# Swarm_Bot_Overall.net
KiCad netlist of a schematic drawn in EAGLE
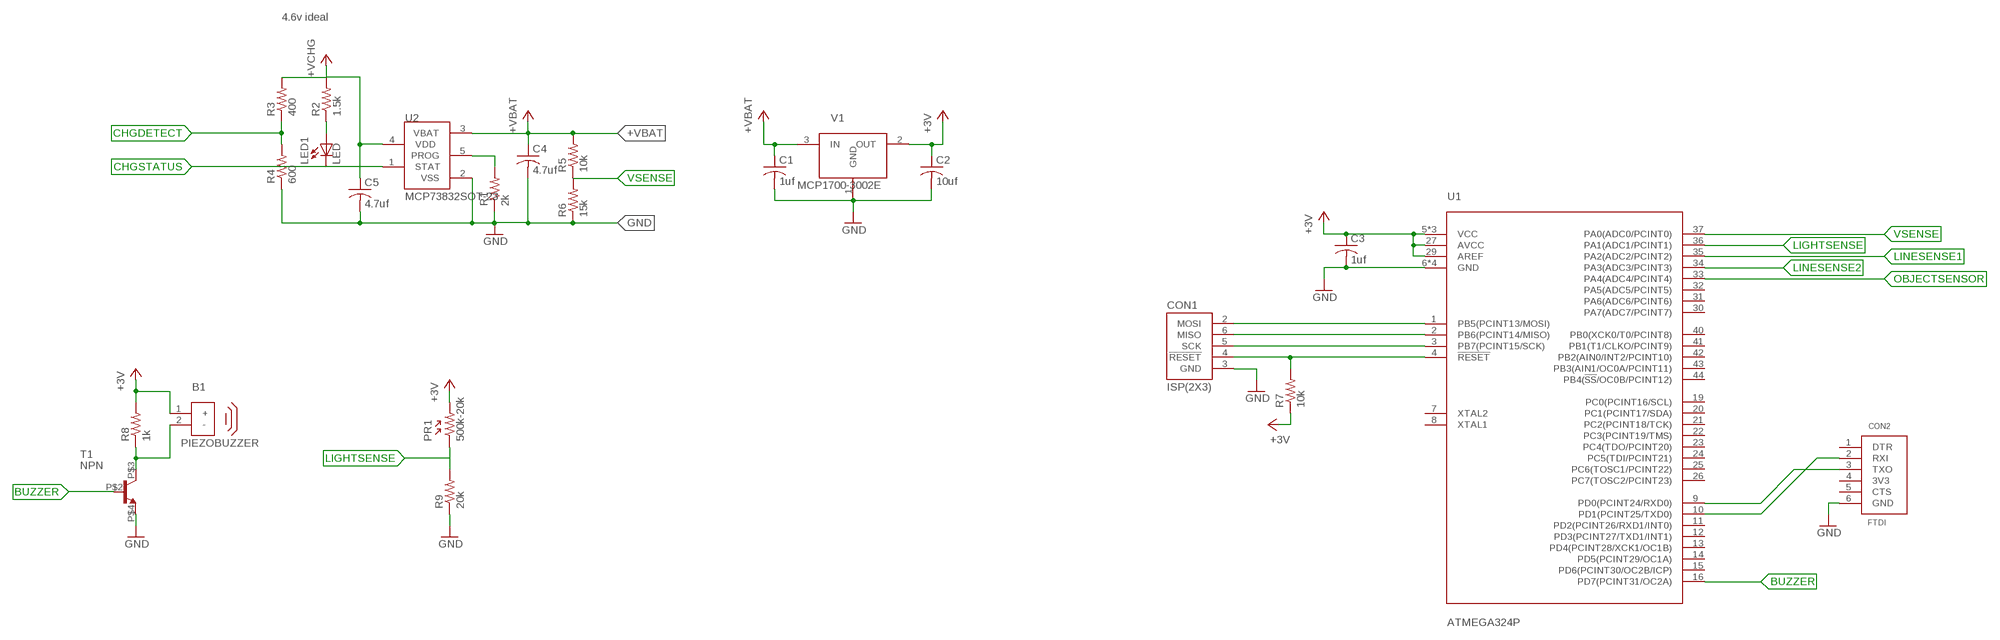
[diagram p0: schematic, sheet 1]

(export (version "E")
  (design (tool "Eeschema 10.0.6"))
  (components
    (comp (ref "B1")
      (value "PIEZOBUZZER")
      (footprint "eagle-import:PIEZOBUZZER")
      (libsource (lib "eagle-import") (part "PIEZOBUZZER"))
    )
    (comp (ref "C1")
      (value "1uf")
      (footprint "eagle-import:0603")
      (libsource (lib "eagle-import") (part "CAP0603"))
    )
    (comp (ref "C2")
      (value "10uf")
      (footprint "eagle-import:0805")
      (libsource (lib "eagle-import") (part "CAP0805"))
    )
    (comp (ref "C3")
      (value "1uf")
      (footprint "eagle-import:0603")
      (libsource (lib "eagle-import") (part "CAP0603"))
    )
    (comp (ref "C4")
      (value "4.7uf")
      (footprint "eagle-import:0603")
      (libsource (lib "eagle-import") (part "CAP0603"))
    )
    (comp (ref "C5")
      (value "4.7uf")
      (footprint "eagle-import:0603")
      (libsource (lib "eagle-import") (part "CAP0603"))
    )
    (comp (ref "CON1")
      (value "ISP(2X3)")
      (footprint "eagle-import:PINHEADER(2X3)")
      (libsource (lib "eagle-import") (part "ISP(2X3)"))
    )
    (comp (ref "CON2")
      (value "FTDI")
      (footprint "eagle-import:PINHEADER(1X6)")
      (libsource (lib "eagle-import") (part "FTDI"))
    )
    (comp (ref "LED1")
      (value "LED")
      (footprint "eagle-import:0603")
      (libsource (lib "eagle-import") (part "LED"))
    )
    (comp (ref "PR1")
      (value "500k-20k")
      (footprint "eagle-import:CDSPHOTOCELL")
      (libsource (lib "eagle-import") (part "CDSPHOTORESISTOR"))
    )
    (comp (ref "R1")
      (value "2k")
      (footprint "eagle-import:0603")
      (libsource (lib "eagle-import") (part "RES0603"))
    )
    (comp (ref "R2")
      (value "1.5k")
      (footprint "eagle-import:0603")
      (libsource (lib "eagle-import") (part "RES0603"))
    )
    (comp (ref "R3")
      (value "400")
      (footprint "eagle-import:0603")
      (libsource (lib "eagle-import") (part "RES0603"))
    )
    (comp (ref "R4")
      (value "600")
      (footprint "eagle-import:0603")
      (libsource (lib "eagle-import") (part "RES0603"))
    )
    (comp (ref "R5")
      (value "10k")
      (footprint "eagle-import:0603")
      (libsource (lib "eagle-import") (part "RES0603"))
    )
    (comp (ref "R6")
      (value "15k")
      (footprint "eagle-import:0603")
      (libsource (lib "eagle-import") (part "RES0603"))
    )
    (comp (ref "R7")
      (value "10k")
      (footprint "eagle-import:0603")
      (libsource (lib "eagle-import") (part "RES0603"))
    )
    (comp (ref "R8")
      (value "1k")
      (footprint "eagle-import:0603")
      (libsource (lib "eagle-import") (part "RES0603"))
    )
    (comp (ref "R9")
      (value "20k")
      (footprint "eagle-import:0603")
      (libsource (lib "eagle-import") (part "RES0603"))
    )
    (comp (ref "T1")
      (value "NPN")
      (footprint "eagle-import:DUMMY")
      (libsource (lib "eagle-import") (part "NPN"))
    )
    (comp (ref "U1")
      (value "ATMEGA324P")
      (footprint "eagle-import:TQFP44")
      (libsource (lib "eagle-import") (part "ATMEGA324P"))
    )
    (comp (ref "U2")
      (value "MCP73832SOT-23")
      (footprint "eagle-import:(OT)SOT-23(5PAD)")
      (libsource (lib "eagle-import") (part "MCP73832SOT-23"))
    )
    (comp (ref "V1")
      (value "MCP1700-3002E")
      (footprint "eagle-import:(TT_NB)SOT-23(3PAD)")
      (libsource (lib "eagle-import") (part "MCP1700-3002E"))
    )
  )
  (nets
    (net (code "1") (name "+3V") (class "Default")
      (node (ref "B1") (pin "1") (pinfunction "+_1") (pintype "bidirectional"))
      (node (ref "C2") (pin "1") (pinfunction "1_1") (pintype "passive"))
      (node (ref "C3") (pin "1") (pinfunction "1_1") (pintype "passive"))
      (node (ref "PR1") (pin "2") (pinfunction "2_2") (pintype "passive"))
      (node (ref "R7") (pin "1") (pinfunction "1_1") (pintype "passive"))
      (node (ref "R8") (pin "2") (pinfunction "2_2") (pintype "passive"))
      (node (ref "U1") (pin "17") (pinfunction "VCC_17") (pintype "bidirectional"))
      (node (ref "U1") (pin "27") (pinfunction "AVCC_27") (pintype "bidirectional"))
      (node (ref "U1") (pin "29") (pinfunction "AREF_29") (pintype "bidirectional"))
      (node (ref "U1") (pin "38") (pinfunction "VCC_38") (pintype "bidirectional"))
      (node (ref "U1") (pin "5") (pinfunction "VCC_5") (pintype "bidirectional"))
      (node (ref "V1") (pin "2") (pinfunction "OUT_2") (pintype "bidirectional"))
    )
    (net (code "2") (name "+VBAT") (class "Default")
      (node (ref "C1") (pin "1") (pinfunction "1_1") (pintype "passive"))
      (node (ref "C4") (pin "1") (pinfunction "1_1") (pintype "passive"))
      (node (ref "R5") (pin "2") (pinfunction "2_2") (pintype "passive"))
      (node (ref "U2") (pin "3") (pinfunction "VBAT_3") (pintype "bidirectional"))
      (node (ref "V1") (pin "3") (pinfunction "IN_3") (pintype "bidirectional"))
    )
    (net (code "3") (name "+VCHG") (class "Default")
      (node (ref "C5") (pin "1") (pinfunction "1_1") (pintype "passive"))
      (node (ref "R2") (pin "2") (pinfunction "2_2") (pintype "passive"))
      (node (ref "R3") (pin "2") (pinfunction "2_2") (pintype "passive"))
      (node (ref "U2") (pin "4") (pinfunction "VDD_4") (pintype "bidirectional"))
    )
    (net (code "4") (name "BUZZER") (class "Default")
      (node (ref "T1") (pin "P$2") (pinfunction "B_P$2") (pintype "passive"))
      (node (ref "U1") (pin "16") (pinfunction "PD7(PCINT31/OC2A)_16") (pintype "bidirectional"))
    )
    (net (code "5") (name "CHGDETECT") (class "Default")
      (node (ref "R3") (pin "1") (pinfunction "1_1") (pintype "passive"))
      (node (ref "R4") (pin "2") (pinfunction "2_2") (pintype "passive"))
    )
    (net (code "6") (name "CHGSTATUS") (class "Default")
      (node (ref "LED1") (pin "1") (pinfunction "C_1") (pintype "passive"))
      (node (ref "U2") (pin "1") (pinfunction "STAT_1") (pintype "bidirectional"))
    )
    (net (code "7") (name "GND") (class "Default")
      (node (ref "C1") (pin "2") (pinfunction "2_2") (pintype "passive"))
      (node (ref "C2") (pin "2") (pinfunction "2_2") (pintype "passive"))
      (node (ref "C3") (pin "2") (pinfunction "2_2") (pintype "passive"))
      (node (ref "C4") (pin "2") (pinfunction "2_2") (pintype "passive"))
      (node (ref "C5") (pin "2") (pinfunction "2_2") (pintype "passive"))
      (node (ref "CON1") (pin "3") (pinfunction "GND_3") (pintype "bidirectional"))
      (node (ref "CON2") (pin "6") (pinfunction "GND_6") (pintype "bidirectional"))
      (node (ref "R1") (pin "1") (pinfunction "1_1") (pintype "passive"))
      (node (ref "R4") (pin "1") (pinfunction "1_1") (pintype "passive"))
      (node (ref "R6") (pin "1") (pinfunction "1_1") (pintype "passive"))
      (node (ref "R9") (pin "1") (pinfunction "1_1") (pintype "passive"))
      (node (ref "T1") (pin "P$4") (pinfunction "E_P$4") (pintype "passive"))
      (node (ref "U1") (pin "18") (pinfunction "GND_18") (pintype "bidirectional"))
      (node (ref "U1") (pin "28") (pinfunction "GND_28") (pintype "bidirectional"))
      (node (ref "U1") (pin "39") (pinfunction "GND_39") (pintype "bidirectional"))
      (node (ref "U1") (pin "6") (pinfunction "GND_6") (pintype "bidirectional"))
      (node (ref "U2") (pin "2") (pinfunction "VSS_2") (pintype "bidirectional"))
      (node (ref "V1") (pin "1") (pinfunction "GND_1") (pintype "bidirectional"))
    )
    (net (code "8") (name "LIGHTSENSE") (class "Default")
      (node (ref "PR1") (pin "1") (pinfunction "1_1") (pintype "passive"))
      (node (ref "R9") (pin "2") (pinfunction "2_2") (pintype "passive"))
      (node (ref "U1") (pin "36") (pinfunction "PA1(ADC1/PCINT1)_36") (pintype "bidirectional"))
    )
    (net (code "9") (name "LINESENSE1") (class "Default")
      (node (ref "U1") (pin "35") (pinfunction "PA2(ADC2/PCINT2)_35") (pintype "bidirectional"))
    )
    (net (code "10") (name "LINESENSE2") (class "Default")
      (node (ref "U1") (pin "34") (pinfunction "PA3(ADC3/PCINT3)_34") (pintype "bidirectional"))
    )
    (net (code "11") (name "Net-(B1--)") (class "Default")
      (node (ref "B1") (pin "2") (pinfunction "-_2") (pintype "bidirectional"))
      (node (ref "R8") (pin "1") (pinfunction "1_1") (pintype "passive"))
      (node (ref "T1") (pin "P$3") (pinfunction "C_P$3") (pintype "passive"))
    )
    (net (code "12") (name "Net-(CON1-MISO)") (class "Default")
      (node (ref "CON1") (pin "6") (pinfunction "MISO_6") (pintype "bidirectional"))
      (node (ref "U1") (pin "2") (pinfunction "PB6(PCINT14/MISO)_2") (pintype "bidirectional"))
    )
    (net (code "13") (name "Net-(CON1-MOSI)") (class "Default")
      (node (ref "CON1") (pin "2") (pinfunction "MOSI_2") (pintype "bidirectional"))
      (node (ref "U1") (pin "1") (pinfunction "PB5(PCINT13/MOSI)_1") (pintype "bidirectional"))
    )
    (net (code "14") (name "Net-(CON1-SCK)") (class "Default")
      (node (ref "CON1") (pin "5") (pinfunction "SCK_5") (pintype "bidirectional"))
      (node (ref "U1") (pin "3") (pinfunction "PB7(PCINT15/SCK)_3") (pintype "bidirectional"))
    )
    (net (code "15") (name "Net-(CON1-~{RESET})") (class "Default")
      (node (ref "CON1") (pin "4") (pinfunction "~{RESET}_4") (pintype "bidirectional"))
      (node (ref "R7") (pin "2") (pinfunction "2_2") (pintype "passive"))
      (node (ref "U1") (pin "4") (pinfunction "~{RESET}_4") (pintype "bidirectional"))
    )
    (net (code "16") (name "Net-(CON2-RXI)") (class "Default")
      (node (ref "CON2") (pin "2") (pinfunction "RXI_2") (pintype "bidirectional"))
      (node (ref "U1") (pin "10") (pinfunction "PD1(PCINT25/TXD0)_10") (pintype "bidirectional"))
    )
    (net (code "17") (name "Net-(CON2-TXO)") (class "Default")
      (node (ref "CON2") (pin "3") (pinfunction "TXO_3") (pintype "bidirectional"))
      (node (ref "U1") (pin "9") (pinfunction "PD0(PCINT24/RXD0)_9") (pintype "bidirectional"))
    )
    (net (code "18") (name "Net-(LED1-A)") (class "Default")
      (node (ref "LED1") (pin "2") (pinfunction "A_2") (pintype "passive"))
      (node (ref "R2") (pin "1") (pinfunction "1_1") (pintype "passive"))
    )
    (net (code "19") (name "Net-(U2-PROG)") (class "Default")
      (node (ref "R1") (pin "2") (pinfunction "2_2") (pintype "passive"))
      (node (ref "U2") (pin "5") (pinfunction "PROG_5") (pintype "bidirectional"))
    )
    (net (code "20") (name "OBJECTSENSOR") (class "Default")
      (node (ref "U1") (pin "33") (pinfunction "PA4(ADC4/PCINT4)_33") (pintype "bidirectional"))
    )
    (net (code "21") (name "VSENSE") (class "Default")
      (node (ref "R5") (pin "1") (pinfunction "1_1") (pintype "passive"))
      (node (ref "R6") (pin "2") (pinfunction "2_2") (pintype "passive"))
      (node (ref "U1") (pin "37") (pinfunction "PA0(ADC0/PCINT0)_37") (pintype "bidirectional"))
    )
    (net (code "22") (name "unconnected-(CON2-3V3-Pad4)") (class "Default")
      (node (ref "CON2") (pin "4") (pinfunction "3V3_4") (pintype "bidirectional"))
    )
    (net (code "23") (name "unconnected-(CON2-CTS-Pad5)") (class "Default")
      (node (ref "CON2") (pin "5") (pinfunction "CTS_5") (pintype "bidirectional"))
    )
    (net (code "24") (name "unconnected-(CON2-DTR-Pad1)") (class "Default")
      (node (ref "CON2") (pin "1") (pinfunction "DTR_1") (pintype "bidirectional"))
    )
    (net (code "25") (name "unconnected-(U1-PA5(ADC5{slash}PCINT5)-Pad32)") (class "Default")
      (node (ref "U1") (pin "32") (pinfunction "PA5(ADC5/PCINT5)_32") (pintype "bidirectional"))
    )
    (net (code "26") (name "unconnected-(U1-PA6(ADC6{slash}PCINT6)-Pad31)") (class "Default")
      (node (ref "U1") (pin "31") (pinfunction "PA6(ADC6/PCINT6)_31") (pintype "bidirectional"))
    )
    (net (code "27") (name "unconnected-(U1-PA7(ADC7{slash}PCINT7)-Pad30)") (class "Default")
      (node (ref "U1") (pin "30") (pinfunction "PA7(ADC7/PCINT7)_30") (pintype "bidirectional"))
    )
    (net (code "28") (name "unconnected-(U1-PB0(XCK0{slash}T0{slash}PCINT8)-Pad40)") (class "Default")
      (node (ref "U1") (pin "40") (pinfunction "PB0(XCK0/T0/PCINT8)_40") (pintype "bidirectional"))
    )
    (net (code "29") (name "unconnected-(U1-PB1(T1{slash}CLKO{slash}PCINT9)-Pad41)") (class "Default")
      (node (ref "U1") (pin "41") (pinfunction "PB1(T1/CLKO/PCINT9)_41") (pintype "bidirectional"))
    )
    (net (code "30") (name "unconnected-(U1-PB2(AIN0{slash}INT2{slash}PCINT10)-Pad42)") (class "Default")
      (node (ref "U1") (pin "42") (pinfunction "PB2(AIN0/INT2/PCINT10)_42") (pintype "bidirectional"))
    )
    (net (code "31") (name "unconnected-(U1-PB3(AIN1{slash}OC0A{slash}PCINT11)-Pad43)") (class "Default")
      (node (ref "U1") (pin "43") (pinfunction "PB3(AIN1/OC0A/PCINT11)_43") (pintype "bidirectional"))
    )
    (net (code "32") (name "unconnected-(U1-PB4(~{SS}{slash}OC0B{slash}PCINT12)-Pad44)") (class "Default")
      (node (ref "U1") (pin "44") (pinfunction "PB4(~{SS}/OC0B/PCINT12)_44") (pintype "bidirectional"))
    )
    (net (code "33") (name "unconnected-(U1-PC0(PCINT16{slash}SCL)-Pad19)") (class "Default")
      (node (ref "U1") (pin "19") (pinfunction "PC0(PCINT16/SCL)_19") (pintype "bidirectional"))
    )
    (net (code "34") (name "unconnected-(U1-PC1(PCINT17{slash}SDA)-Pad20)") (class "Default")
      (node (ref "U1") (pin "20") (pinfunction "PC1(PCINT17/SDA)_20") (pintype "bidirectional"))
    )
    (net (code "35") (name "unconnected-(U1-PC2(PCINT18{slash}TCK)-Pad21)") (class "Default")
      (node (ref "U1") (pin "21") (pinfunction "PC2(PCINT18/TCK)_21") (pintype "bidirectional"))
    )
    (net (code "36") (name "unconnected-(U1-PC3(PCINT19{slash}TMS)-Pad22)") (class "Default")
      (node (ref "U1") (pin "22") (pinfunction "PC3(PCINT19/TMS)_22") (pintype "bidirectional"))
    )
    (net (code "37") (name "unconnected-(U1-PC4(TDO{slash}PCINT20)-Pad23)") (class "Default")
      (node (ref "U1") (pin "23") (pinfunction "PC4(TDO/PCINT20)_23") (pintype "bidirectional"))
    )
    (net (code "38") (name "unconnected-(U1-PC5(TDI{slash}PCINT21)-Pad24)") (class "Default")
      (node (ref "U1") (pin "24") (pinfunction "PC5(TDI/PCINT21)_24") (pintype "bidirectional"))
    )
    (net (code "39") (name "unconnected-(U1-PC6(TOSC1{slash}PCINT22)-Pad25)") (class "Default")
      (node (ref "U1") (pin "25") (pinfunction "PC6(TOSC1/PCINT22)_25") (pintype "bidirectional"))
    )
    (net (code "40") (name "unconnected-(U1-PC7(TOSC2{slash}PCINT23)-Pad26)") (class "Default")
      (node (ref "U1") (pin "26") (pinfunction "PC7(TOSC2/PCINT23)_26") (pintype "bidirectional"))
    )
    (net (code "41") (name "unconnected-(U1-PD2(PCINT26{slash}RXD1{slash}INT0)-Pad11)") (class "Default")
      (node (ref "U1") (pin "11") (pinfunction "PD2(PCINT26/RXD1/INT0)_11") (pintype "bidirectional"))
    )
    (net (code "42") (name "unconnected-(U1-PD3(PCINT27{slash}TXD1{slash}INT1)-Pad12)") (class "Default")
      (node (ref "U1") (pin "12") (pinfunction "PD3(PCINT27/TXD1/INT1)_12") (pintype "bidirectional"))
    )
    (net (code "43") (name "unconnected-(U1-PD4(PCINT28{slash}XCK1{slash}OC1B)-Pad13)") (class "Default")
      (node (ref "U1") (pin "13") (pinfunction "PD4(PCINT28/XCK1/OC1B)_13") (pintype "bidirectional"))
    )
    (net (code "44") (name "unconnected-(U1-PD5(PCINT29{slash}OC1A)-Pad14)") (class "Default")
      (node (ref "U1") (pin "14") (pinfunction "PD5(PCINT29/OC1A)_14") (pintype "bidirectional"))
    )
    (net (code "45") (name "unconnected-(U1-PD6(PCINT30{slash}OC2B{slash}ICP)-Pad15)") (class "Default")
      (node (ref "U1") (pin "15") (pinfunction "PD6(PCINT30/OC2B/ICP)_15") (pintype "bidirectional"))
    )
    (net (code "46") (name "unconnected-(U1-XTAL1-Pad8)") (class "Default")
      (node (ref "U1") (pin "8") (pinfunction "XTAL1_8") (pintype "bidirectional"))
    )
    (net (code "47") (name "unconnected-(U1-XTAL2-Pad7)") (class "Default")
      (node (ref "U1") (pin "7") (pinfunction "XTAL2_7") (pintype "bidirectional"))
    )
  )
)
